# atmel_eagle.net
KiCad netlist of a schematic drawn in EAGLE
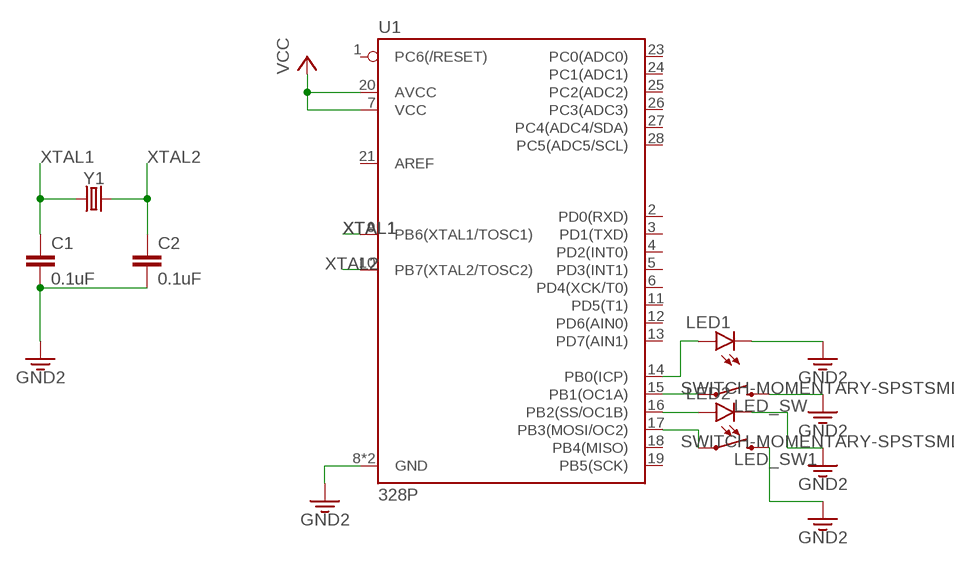
[diagram p0: schematic, sheet 1]

(export (version "E")
  (design (tool "Eeschema 10.0.6"))
  (components
    (comp (ref "C1")
      (value "0.1uF")
      (footprint "eagle-import:CAP-PTH-SMALL-KIT")
      (libsource (lib "eagle-import") (part "0.1UF-KIT-EZ-50V-20%"))
    )
    (comp (ref "C2")
      (value "0.1uF")
      (footprint "eagle-import:CAP-PTH-SMALL-KIT")
      (libsource (lib "eagle-import") (part "0.1UF-KIT-EZ-50V-20%"))
    )
    (comp (ref "LED1")
      (value "LED10MM")
      (footprint "eagle-import:LED10MM")
      (libsource (lib "eagle-import") (part "LED10MM"))
    )
    (comp (ref "LED2")
      (value "LED10MM")
      (footprint "eagle-import:LED10MM")
      (libsource (lib "eagle-import") (part "LED10MM"))
    )
    (comp (ref "LED_SW")
      (value "SWITCH-MOMENTARY-SPSTSMD-3")
      (footprint "eagle-import:TACTILE_SWITCH_SMD-3")
      (libsource (lib "eagle-import") (part "SWITCH-MOMENTARY-SPSTSMD-3"))
    )
    (comp (ref "LED_SW1")
      (value "SWITCH-MOMENTARY-SPSTSMD-3")
      (footprint "eagle-import:TACTILE_SWITCH_SMD-3")
      (libsource (lib "eagle-import") (part "SWITCH-MOMENTARY-SPSTSMD-3"))
    )
    (comp (ref "U1")
      (value "328P")
      (footprint "eagle-import:DIP28")
      (libsource (lib "eagle-import") (part "ATMEGA328P_PDIP"))
    )
    (comp (ref "Y1")
      (value "CRYSTALPTH-HC49US")
      (footprint "eagle-import:HC49US")
      (libsource (lib "eagle-import") (part "CRYSTALPTH-HC49US"))
    )
  )
  (nets
    (net (code "1") (name "/XTAL1") (class "Default")
      (node (ref "C1") (pin "1") (pinfunction "1_1") (pintype "passive"))
      (node (ref "U1") (pin "9") (pinfunction "PB6(XTAL1/TOSC1)_9") (pintype "bidirectional"))
      (node (ref "Y1") (pin "1") (pinfunction "1_1") (pintype "passive"))
    )
    (net (code "2") (name "/XTAL2") (class "Default")
      (node (ref "C2") (pin "1") (pinfunction "1_1") (pintype "passive"))
      (node (ref "U1") (pin "10") (pinfunction "PB7(XTAL2/TOSC2)_10") (pintype "bidirectional"))
      (node (ref "Y1") (pin "2") (pinfunction "2_2") (pintype "passive"))
    )
    (net (code "3") (name "GND2") (class "Default")
      (node (ref "C1") (pin "2") (pinfunction "2_2") (pintype "passive"))
      (node (ref "C2") (pin "2") (pinfunction "2_2") (pintype "passive"))
      (node (ref "LED1") (pin "K") (pinfunction "C_K") (pintype "passive"))
      (node (ref "LED2") (pin "K") (pinfunction "C_K") (pintype "passive"))
      (node (ref "LED_SW") (pin "4") (pinfunction "2_4") (pintype "passive"))
      (node (ref "LED_SW1") (pin "4") (pinfunction "2_4") (pintype "passive"))
      (node (ref "U1") (pin "22") (pinfunction "GND_22") (pintype "bidirectional"))
      (node (ref "U1") (pin "8") (pinfunction "GND_8") (pintype "bidirectional"))
    )
    (net (code "4") (name "Net-(U1-PB0(ICP))") (class "Default")
      (node (ref "LED1") (pin "A") (pinfunction "A_A") (pintype "passive"))
      (node (ref "U1") (pin "14") (pinfunction "PB0(ICP)_14") (pintype "bidirectional"))
    )
    (net (code "5") (name "Net-(U1-PB1(OC1A))") (class "Default")
      (node (ref "LED_SW") (pin "1") (pinfunction "1_1") (pintype "passive"))
      (node (ref "U1") (pin "15") (pinfunction "PB1(OC1A)_15") (pintype "bidirectional"))
    )
    (net (code "6") (name "Net-(U1-PB2(SS{slash}OC1B))") (class "Default")
      (node (ref "LED2") (pin "A") (pinfunction "A_A") (pintype "passive"))
      (node (ref "U1") (pin "16") (pinfunction "PB2(SS/OC1B)_16") (pintype "bidirectional"))
    )
    (net (code "7") (name "Net-(U1-PB3(MOSI{slash}OC2))") (class "Default")
      (node (ref "LED_SW1") (pin "1") (pinfunction "1_1") (pintype "passive"))
      (node (ref "U1") (pin "17") (pinfunction "PB3(MOSI/OC2)_17") (pintype "bidirectional"))
    )
    (net (code "8") (name "VCC") (class "Default")
      (node (ref "U1") (pin "20") (pinfunction "AVCC_20") (pintype "bidirectional"))
      (node (ref "U1") (pin "7") (pinfunction "VCC_7") (pintype "bidirectional"))
    )
    (net (code "9") (name "unconnected-(U1-AREF-Pad21)") (class "Default")
      (node (ref "U1") (pin "21") (pinfunction "AREF_21") (pintype "bidirectional"))
    )
    (net (code "10") (name "unconnected-(U1-PB4(MISO)-Pad18)") (class "Default")
      (node (ref "U1") (pin "18") (pinfunction "PB4(MISO)_18") (pintype "bidirectional"))
    )
    (net (code "11") (name "unconnected-(U1-PB5(SCK)-Pad19)") (class "Default")
      (node (ref "U1") (pin "19") (pinfunction "PB5(SCK)_19") (pintype "bidirectional"))
    )
    (net (code "12") (name "unconnected-(U1-PC0(ADC0)-Pad23)") (class "Default")
      (node (ref "U1") (pin "23") (pinfunction "PC0(ADC0)_23") (pintype "bidirectional"))
    )
    (net (code "13") (name "unconnected-(U1-PC1(ADC1)-Pad24)") (class "Default")
      (node (ref "U1") (pin "24") (pinfunction "PC1(ADC1)_24") (pintype "bidirectional"))
    )
    (net (code "14") (name "unconnected-(U1-PC2(ADC2)-Pad25)") (class "Default")
      (node (ref "U1") (pin "25") (pinfunction "PC2(ADC2)_25") (pintype "bidirectional"))
    )
    (net (code "15") (name "unconnected-(U1-PC3(ADC3)-Pad26)") (class "Default")
      (node (ref "U1") (pin "26") (pinfunction "PC3(ADC3)_26") (pintype "bidirectional"))
    )
    (net (code "16") (name "unconnected-(U1-PC4(ADC4{slash}SDA)-Pad27)") (class "Default")
      (node (ref "U1") (pin "27") (pinfunction "PC4(ADC4/SDA)_27") (pintype "bidirectional"))
    )
    (net (code "17") (name "unconnected-(U1-PC5(ADC5{slash}SCL)-Pad28)") (class "Default")
      (node (ref "U1") (pin "28") (pinfunction "PC5(ADC5/SCL)_28") (pintype "bidirectional"))
    )
    (net (code "18") (name "unconnected-(U1-PC6({slash}RESET)-Pad1)") (class "Default")
      (node (ref "U1") (pin "1") (pinfunction "PC6(/RESET)_1") (pintype "bidirectional"))
    )
    (net (code "19") (name "unconnected-(U1-PD0(RXD)-Pad2)") (class "Default")
      (node (ref "U1") (pin "2") (pinfunction "PD0(RXD)_2") (pintype "bidirectional"))
    )
    (net (code "20") (name "unconnected-(U1-PD1(TXD)-Pad3)") (class "Default")
      (node (ref "U1") (pin "3") (pinfunction "PD1(TXD)_3") (pintype "bidirectional"))
    )
    (net (code "21") (name "unconnected-(U1-PD2(INT0)-Pad4)") (class "Default")
      (node (ref "U1") (pin "4") (pinfunction "PD2(INT0)_4") (pintype "bidirectional"))
    )
    (net (code "22") (name "unconnected-(U1-PD3(INT1)-Pad5)") (class "Default")
      (node (ref "U1") (pin "5") (pinfunction "PD3(INT1)_5") (pintype "bidirectional"))
    )
    (net (code "23") (name "unconnected-(U1-PD4(XCK{slash}T0)-Pad6)") (class "Default")
      (node (ref "U1") (pin "6") (pinfunction "PD4(XCK/T0)_6") (pintype "bidirectional"))
    )
    (net (code "24") (name "unconnected-(U1-PD5(T1)-Pad11)") (class "Default")
      (node (ref "U1") (pin "11") (pinfunction "PD5(T1)_11") (pintype "bidirectional"))
    )
    (net (code "25") (name "unconnected-(U1-PD6(AIN0)-Pad12)") (class "Default")
      (node (ref "U1") (pin "12") (pinfunction "PD6(AIN0)_12") (pintype "bidirectional"))
    )
    (net (code "26") (name "unconnected-(U1-PD7(AIN1)-Pad13)") (class "Default")
      (node (ref "U1") (pin "13") (pinfunction "PD7(AIN1)_13") (pintype "bidirectional"))
    )
  )
)
